# Attenuator_Channel.net
KiCad netlist of a schematic drawn in Altium Designer
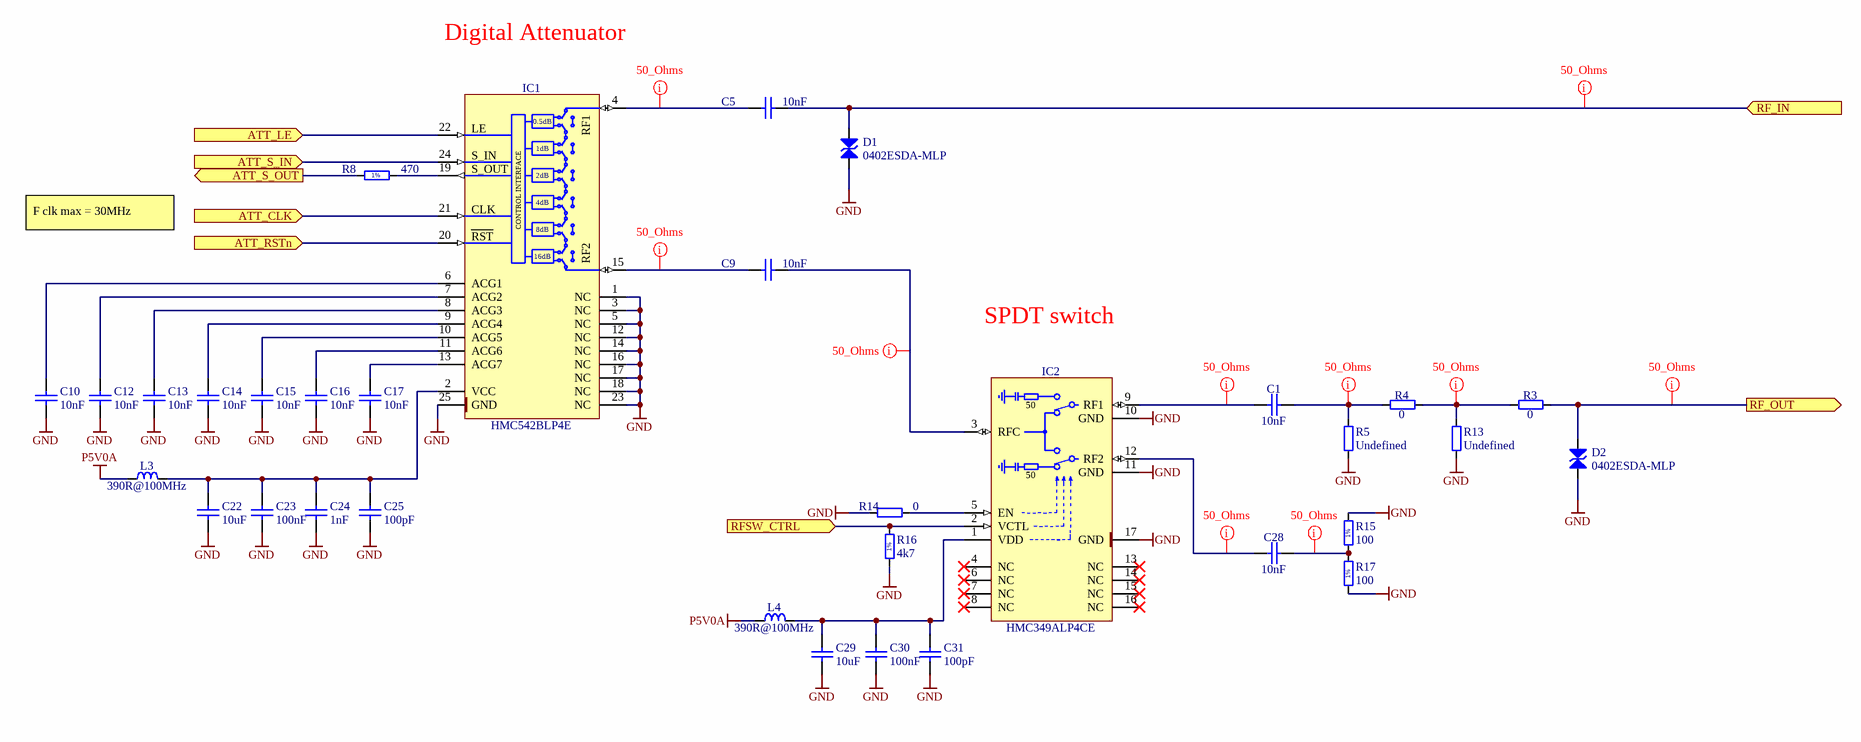
[diagram p0: Attenuator_Channel.SchDoc]

(export (version "E")
  (design (tool "Eeschema 10.0.6"))
  (components
    (comp (ref "C1")
      (value "10nF")
      (footprint "CAPC1005X55N")
      (description "Non-polarised capacitor")
      (fields
        (field (name "PART NUMBER") "CC0402_10NF_16V_10%_X7R")
        (field (name "VOLTAGE") "16V")
        (field (name "AUTHOR") "CERN DEM JLC")
      )
      (libsource (lib "Capacitors") (part "Capacitor - non polarized"))
    )
    (comp (ref "C5")
      (value "10nF")
      (footprint "CAPC1005X55N")
      (description "Non-polarised capacitor")
      (fields
        (field (name "PART NUMBER") "CC0402_10NF_16V_10%_X7R")
        (field (name "VOLTAGE") "16V")
        (field (name "AUTHOR") "CERN DEM JLC")
      )
      (libsource (lib "Capacitors") (part "Capacitor - non polarized"))
    )
    (comp (ref "C9")
      (value "10nF")
      (footprint "CAPC1005X55N")
      (description "Non-polarised capacitor")
      (fields
        (field (name "PART NUMBER") "CC0402_10NF_16V_10%_X7R")
        (field (name "VOLTAGE") "16V")
        (field (name "AUTHOR") "CERN DEM JLC")
      )
      (libsource (lib "Capacitors") (part "Capacitor - non polarized"))
    )
    (comp (ref "C10")
      (value "10nF")
      (footprint "CAPC1005X55N")
      (description "Non-polarised capacitor")
      (fields
        (field (name "PART NUMBER") "CC0402_10NF_16V_10%_X7R")
        (field (name "VOLTAGE") "16V")
        (field (name "AUTHOR") "CERN DEM JLC")
      )
      (libsource (lib "Capacitors") (part "Capacitor - non polarized"))
    )
    (comp (ref "C12")
      (value "10nF")
      (footprint "CAPC1005X55N")
      (description "Non-polarised capacitor")
      (fields
        (field (name "PART NUMBER") "CC0402_10NF_16V_10%_X7R")
        (field (name "VOLTAGE") "16V")
        (field (name "AUTHOR") "CERN DEM JLC")
      )
      (libsource (lib "Capacitors") (part "Capacitor - non polarized"))
    )
    (comp (ref "C13")
      (value "10nF")
      (footprint "CAPC1005X55N")
      (description "Non-polarised capacitor")
      (fields
        (field (name "PART NUMBER") "CC0402_10NF_16V_10%_X7R")
        (field (name "VOLTAGE") "16V")
        (field (name "AUTHOR") "CERN DEM JLC")
      )
      (libsource (lib "Capacitors") (part "Capacitor - non polarized"))
    )
    (comp (ref "C14")
      (value "10nF")
      (footprint "CAPC1005X55N")
      (description "Non-polarised capacitor")
      (fields
        (field (name "PART NUMBER") "CC0402_10NF_16V_10%_X7R")
        (field (name "VOLTAGE") "16V")
        (field (name "AUTHOR") "CERN DEM JLC")
      )
      (libsource (lib "Capacitors") (part "Capacitor - non polarized"))
    )
    (comp (ref "C15")
      (value "10nF")
      (footprint "CAPC1005X55N")
      (description "Non-polarised capacitor")
      (fields
        (field (name "PART NUMBER") "CC0402_10NF_16V_10%_X7R")
        (field (name "VOLTAGE") "16V")
        (field (name "AUTHOR") "CERN DEM JLC")
      )
      (libsource (lib "Capacitors") (part "Capacitor - non polarized"))
    )
    (comp (ref "C16")
      (value "10nF")
      (footprint "CAPC1005X55N")
      (description "Non-polarised capacitor")
      (fields
        (field (name "PART NUMBER") "CC0402_10NF_16V_10%_X7R")
        (field (name "VOLTAGE") "16V")
        (field (name "AUTHOR") "CERN DEM JLC")
      )
      (libsource (lib "Capacitors") (part "Capacitor - non polarized"))
    )
    (comp (ref "C17")
      (value "10nF")
      (footprint "CAPC1005X55N")
      (description "Non-polarised capacitor")
      (fields
        (field (name "PART NUMBER") "CC0402_10NF_16V_10%_X7R")
        (field (name "VOLTAGE") "16V")
        (field (name "AUTHOR") "CERN DEM JLC")
      )
      (libsource (lib "Capacitors") (part "Capacitor - non polarized"))
    )
    (comp (ref "C22")
      (value "10uF")
      (footprint "CAPC1608X80N")
      (description "Non-polarised capacitor")
      (fields
        (field (name "PART NUMBER") "CC0603_10UF_16V_20%_X5R")
        (field (name "VOLTAGE") "16V")
        (field (name "AUTHOR") "CERN DEM MR")
      )
      (libsource (lib "Capacitors") (part "Capacitor - non polarized"))
    )
    (comp (ref "C23")
      (value "100nF")
      (footprint "CAPC1005X55N")
      (description "Non-polarised capacitor")
      (fields
        (field (name "PART NUMBER") "CC0402_100NF_16V_10%_X5R")
        (field (name "VOLTAGE") "16V")
        (field (name "AUTHOR") "CERN DEM JLC")
      )
      (libsource (lib "Capacitors") (part "Capacitor - non polarized"))
    )
    (comp (ref "C24")
      (value "1nF")
      (footprint "CAPC1005X55N")
      (description "Non-polarised capacitor")
      (fields
        (field (name "PART NUMBER") "CC0402_1NF_50V_10%_X7R")
        (field (name "VOLTAGE") "50V")
        (field (name "AUTHOR") "CERN DEM JLC")
      )
      (libsource (lib "Capacitors") (part "Capacitor - non polarized"))
    )
    (comp (ref "C25")
      (value "100pF")
      (footprint "CAPC1005X55N")
      (description "Non-polarised capacitor")
      (fields
        (field (name "PART NUMBER") "CC0402_100PF_50V_5%_C0G")
        (field (name "VOLTAGE") "50V")
        (field (name "AUTHOR") "CERN DEM JLC")
      )
      (libsource (lib "Capacitors") (part "Capacitor - non polarized"))
    )
    (comp (ref "C28")
      (value "10nF")
      (footprint "CAPC1005X55N")
      (description "Non-polarised capacitor")
      (fields
        (field (name "PART NUMBER") "CC0402_10NF_16V_10%_X7R")
        (field (name "VOLTAGE") "16V")
        (field (name "AUTHOR") "CERN DEM JLC")
      )
      (libsource (lib "Capacitors") (part "Capacitor - non polarized"))
    )
    (comp (ref "C29")
      (value "10uF")
      (footprint "CAPC1608X80N")
      (description "Non-polarised capacitor")
      (fields
        (field (name "PART NUMBER") "CC0603_10UF_16V_20%_X5R")
        (field (name "VOLTAGE") "16V")
        (field (name "AUTHOR") "CERN DEM MR")
      )
      (libsource (lib "Capacitors") (part "Capacitor - non polarized"))
    )
    (comp (ref "C30")
      (value "100nF")
      (footprint "CAPC1005X55N")
      (description "Non-polarised capacitor")
      (fields
        (field (name "PART NUMBER") "CC0402_100NF_16V_10%_X5R")
        (field (name "VOLTAGE") "16V")
        (field (name "AUTHOR") "CERN DEM JLC")
      )
      (libsource (lib "Capacitors") (part "Capacitor - non polarized"))
    )
    (comp (ref "C31")
      (value "100pF")
      (footprint "CAPC1005X55N")
      (description "Non-polarised capacitor")
      (fields
        (field (name "PART NUMBER") "CC0402_100PF_50V_5%_C0G")
        (field (name "VOLTAGE") "50V")
        (field (name "AUTHOR") "CERN DEM JLC")
      )
      (libsource (lib "Capacitors") (part "Capacitor - non polarized"))
    )
    (comp (ref "D1")
      (value "0402ESDA-MLP")
      (footprint "EATON_0402ESDA-MLP")
      (description "Transient Voltage Suppressor Diode (Bi-Directional)")
      (fields
        (field (name "VOLTAGE") "8kV")
        (field (name "MANUFACTURER") "EATON")
        (field (name "AUTHOR") "CERN DEM MR")
      )
      (libsource (lib "ICs And Semiconductors") (part "Diode TVS Bi-Directional"))
    )
    (comp (ref "D2")
      (value "0402ESDA-MLP")
      (footprint "EATON_0402ESDA-MLP")
      (description "Transient Voltage Suppressor Diode (Bi-Directional)")
      (fields
        (field (name "VOLTAGE") "8kV")
        (field (name "MANUFACTURER") "EATON")
        (field (name "AUTHOR") "CERN DEM MR")
      )
      (libsource (lib "ICs And Semiconductors") (part "Diode TVS Bi-Directional"))
    )
    (comp (ref "IC1")
      (value "HMC542BLP4E")
      (footprint "QFN50P400X400X100-25N-S295")
      (description "0.5dB LSB GaAs MMIC 6-bit Digital Serial Control Attenuator, DC - 4GHz")
      (fields (field (name "MANUFACTURER") "HITTITE MICROWAVE CORP") (field (name "AUTHOR") "CERN DEM JMW"))
      (libsource (lib "ICs And Semiconductors") (part "HMC542BLP4E"))
    )
    (comp (ref "IC2")
      (value "HMC349ALP4CE")
      (footprint "QFN65P400X400X100-17N-S255")
      (description "DC-4GHz High Isolation SPDT Non-Reflective Switch")
      (fields (field (name "MANUFACTURER") "ANALOG DEVICES") (field (name "AUTHOR") "CERN DEM JLC"))
      (libsource (lib "ICs And Semiconductors") (part "HMC349ALP4CE"))
    )
    (comp (ref "L3")
      (value "390R@100MHz")
      (footprint "INDC1608X95N")
      (description "Inductor")
      (fields
        (field (name "PART NUMBER") "IND0603_TDK_MPZ1608R391A")
        (field (name "POWER") "1.2A")
        (field (name "AUTHOR") "CERN DEM JLC")
      )
      (libsource (lib "Inductors & Transformers") (part "Inductor"))
    )
    (comp (ref "L4")
      (value "390R@100MHz")
      (footprint "INDC1608X95N")
      (description "Inductor")
      (fields
        (field (name "PART NUMBER") "IND0603_TDK_MPZ1608R391A")
        (field (name "POWER") "1.2A")
        (field (name "AUTHOR") "CERN DEM JLC")
      )
      (libsource (lib "Inductors & Transformers") (part "Inductor"))
    )
    (comp (ref "R3")
      (value "0")
      (footprint "RESC1005X40N")
      (description "Resistor")
      (fields
        (field (name "PART NUMBER") "R0402_0R_JUMPER")
        (field (name "MANUFACTURER") "GENERIC")
        (field (name "AUTHOR") "CERN DEM JLC")
      )
      (libsource (lib "Resistors") (part "Resistor"))
    )
    (comp (ref "R4")
      (value "0")
      (footprint "RESC1005X40N")
      (description "Resistor")
      (fields
        (field (name "PART NUMBER") "R0402_0R_JUMPER")
        (field (name "MANUFACTURER") "GENERIC")
        (field (name "AUTHOR") "CERN DEM JLC")
      )
      (libsource (lib "Resistors") (part "Resistor"))
    )
    (comp (ref "R5")
      (value "Undefined")
      (footprint "RESC1005X40N")
      (description "Resistor")
      (fields (field (name "PART NUMBER") "R0402_NO-VALUE") (field (name "AUTHOR") "CERN DEM JLC"))
      (libsource (lib "Resistors") (part "Resistor"))
    )
    (comp (ref "R8")
      (value "470")
      (footprint "RESC1005X40N")
      (description "Resistor - 1%")
      (fields
        (field (name "PART NUMBER") "R0402_470R_1%_0.0625W_100PPM")
        (field (name "POWER") "0.0625W")
        (field (name "AUTHOR") "CERN DEM JLC")
      )
      (libsource (lib "Resistors") (part "Resistor - 1%"))
    )
    (comp (ref "R13")
      (value "Undefined")
      (footprint "RESC1005X40N")
      (description "Resistor")
      (fields (field (name "PART NUMBER") "R0402_NO-VALUE") (field (name "AUTHOR") "CERN DEM JLC"))
      (libsource (lib "Resistors") (part "Resistor"))
    )
    (comp (ref "R14")
      (value "0")
      (footprint "RESC1005X40N")
      (description "Resistor")
      (fields
        (field (name "PART NUMBER") "R0402_0R_JUMPER")
        (field (name "MANUFACTURER") "GENERIC")
        (field (name "AUTHOR") "CERN DEM JLC")
      )
      (libsource (lib "Resistors") (part "Resistor"))
    )
    (comp (ref "R15")
      (value "100")
      (footprint "RESC1005X40N")
      (description "Resistor - 1%")
      (fields
        (field (name "PART NUMBER") "R0402_100R_1%_0.0625W_100PPM")
        (field (name "POWER") "0.0625W")
        (field (name "AUTHOR") "CERN DEM JLC")
      )
      (libsource (lib "Resistors") (part "Resistor - 1%"))
    )
    (comp (ref "R16")
      (value "4k7")
      (footprint "RESC1005X40N")
      (description "Resistor - 1%")
      (fields
        (field (name "PART NUMBER") "R0402_4K7_1%_0.0625W_100PPM")
        (field (name "POWER") "0.0625W")
        (field (name "AUTHOR") "CERN DEM JLC")
      )
      (libsource (lib "Resistors") (part "Resistor - 1%"))
    )
    (comp (ref "R17")
      (value "100")
      (footprint "RESC1005X40N")
      (description "Resistor - 1%")
      (fields
        (field (name "PART NUMBER") "R0402_100R_1%_0.0625W_100PPM")
        (field (name "POWER") "0.0625W")
        (field (name "AUTHOR") "CERN DEM JLC")
      )
      (libsource (lib "Resistors") (part "Resistor - 1%"))
    )
  )
  (nets
    (net (code "1") (name "/ATT_CLK") (class "Default")
      (node (ref "IC1") (pin "21") (pinfunction "SHIFT_CLOCK_21") (pintype "input"))
    )
    (net (code "2") (name "/ATT_LE") (class "Default")
      (node (ref "IC1") (pin "22") (pinfunction "LATCH_ENABLE_22") (pintype "input"))
    )
    (net (code "3") (name "/ATT_RSTn") (class "Default")
      (node (ref "IC1") (pin "20") (pinfunction "~{RESET}_20") (pintype "input"))
    )
    (net (code "4") (name "/ATT_S_IN") (class "Default")
      (node (ref "IC1") (pin "24") (pinfunction "SERIAL_INPUT_24") (pintype "input"))
    )
    (net (code "5") (name "/ATT_S_OUT") (class "Default")
      (node (ref "R8") (pin "1") (pinfunction "1_1") (pintype "passive"))
    )
    (net (code "6") (name "/RFSW_CTRL") (class "Default")
      (node (ref "IC2") (pin "2") (pinfunction "VCTL_2") (pintype "input"))
      (node (ref "R16") (pin "2") (pinfunction "2_2") (pintype "passive"))
    )
    (net (code "7") (name "/RF_IN") (class "Default")
      (node (ref "C5") (pin "2") (pinfunction "2_2") (pintype "passive"))
      (node (ref "D1") (pin "2") (pinfunction "2_2") (pintype "passive"))
    )
    (net (code "8") (name "/RF_OUT") (class "Default")
      (node (ref "D2") (pin "2") (pinfunction "2_2") (pintype "passive"))
      (node (ref "R3") (pin "2") (pinfunction "2_2") (pintype "passive"))
    )
    (net (code "9") (name "GND") (class "Default")
      (node (ref "C10") (pin "1") (pinfunction "1_1") (pintype "passive"))
      (node (ref "C12") (pin "1") (pinfunction "1_1") (pintype "passive"))
      (node (ref "C13") (pin "1") (pinfunction "1_1") (pintype "passive"))
      (node (ref "C14") (pin "1") (pinfunction "1_1") (pintype "passive"))
      (node (ref "C15") (pin "1") (pinfunction "1_1") (pintype "passive"))
      (node (ref "C16") (pin "1") (pinfunction "1_1") (pintype "passive"))
      (node (ref "C17") (pin "1") (pinfunction "1_1") (pintype "passive"))
      (node (ref "C22") (pin "1") (pinfunction "1_1") (pintype "passive"))
      (node (ref "C23") (pin "1") (pinfunction "1_1") (pintype "passive"))
      (node (ref "C24") (pin "1") (pinfunction "1_1") (pintype "passive"))
      (node (ref "C25") (pin "1") (pinfunction "1_1") (pintype "passive"))
      (node (ref "C29") (pin "1") (pinfunction "1_1") (pintype "passive"))
      (node (ref "C30") (pin "1") (pinfunction "1_1") (pintype "passive"))
      (node (ref "C31") (pin "1") (pinfunction "1_1") (pintype "passive"))
      (node (ref "D1") (pin "1") (pinfunction "1_1") (pintype "passive"))
      (node (ref "D2") (pin "1") (pinfunction "1_1") (pintype "passive"))
      (node (ref "IC1") (pin "1") (pinfunction "NC_1") (pintype "passive"))
      (node (ref "IC1") (pin "12") (pinfunction "NC_12") (pintype "passive"))
      (node (ref "IC1") (pin "14") (pinfunction "NC_14") (pintype "passive"))
      (node (ref "IC1") (pin "16") (pinfunction "NC_16") (pintype "passive"))
      (node (ref "IC1") (pin "17") (pinfunction "NC_17") (pintype "passive"))
      (node (ref "IC1") (pin "18") (pinfunction "NC_18") (pintype "passive"))
      (node (ref "IC1") (pin "23") (pinfunction "NC_23") (pintype "passive"))
      (node (ref "IC1") (pin "25") (pinfunction "GND_25") (pintype "power_in"))
      (node (ref "IC1") (pin "3") (pinfunction "NC_3") (pintype "passive"))
      (node (ref "IC1") (pin "5") (pinfunction "NC_5") (pintype "passive"))
      (node (ref "IC2") (pin "10") (pinfunction "GND_10") (pintype "power_in"))
      (node (ref "IC2") (pin "11") (pinfunction "GND_11") (pintype "power_in"))
      (node (ref "IC2") (pin "17") (pinfunction "GND_17") (pintype "power_in"))
      (node (ref "R13") (pin "1") (pinfunction "1_1") (pintype "passive"))
      (node (ref "R14") (pin "1") (pinfunction "1_1") (pintype "passive"))
      (node (ref "R15") (pin "2") (pinfunction "2_2") (pintype "passive"))
      (node (ref "R16") (pin "1") (pinfunction "1_1") (pintype "passive"))
      (node (ref "R17") (pin "1") (pinfunction "1_1") (pintype "passive"))
      (node (ref "R5") (pin "1") (pinfunction "1_1") (pintype "passive"))
    )
    (net (code "10") (name "Net-(C1-Pad2)") (class "Default")
      (node (ref "C1") (pin "2") (pinfunction "2_2") (pintype "passive"))
      (node (ref "R4") (pin "1") (pinfunction "1_1") (pintype "passive"))
      (node (ref "R5") (pin "2") (pinfunction "2_2") (pintype "passive"))
    )
    (net (code "11") (name "Net-(C28-Pad2)") (class "Default")
      (node (ref "C28") (pin "2") (pinfunction "2_2") (pintype "passive"))
      (node (ref "R15") (pin "1") (pinfunction "1_1") (pintype "passive"))
      (node (ref "R17") (pin "2") (pinfunction "2_2") (pintype "passive"))
    )
    (net (code "12") (name "Net-(IC1-ACG1)") (class "Default")
      (node (ref "C10") (pin "2") (pinfunction "2_2") (pintype "passive"))
      (node (ref "IC1") (pin "6") (pinfunction "ACG1_6") (pintype "passive"))
    )
    (net (code "13") (name "Net-(IC1-ACG2)") (class "Default")
      (node (ref "C12") (pin "2") (pinfunction "2_2") (pintype "passive"))
      (node (ref "IC1") (pin "7") (pinfunction "ACG2_7") (pintype "passive"))
    )
    (net (code "14") (name "Net-(IC1-ACG3)") (class "Default")
      (node (ref "C13") (pin "2") (pinfunction "2_2") (pintype "passive"))
      (node (ref "IC1") (pin "8") (pinfunction "ACG3_8") (pintype "passive"))
    )
    (net (code "15") (name "Net-(IC1-ACG4)") (class "Default")
      (node (ref "C14") (pin "2") (pinfunction "2_2") (pintype "passive"))
      (node (ref "IC1") (pin "9") (pinfunction "ACG4_9") (pintype "passive"))
    )
    (net (code "16") (name "Net-(IC1-ACG5)") (class "Default")
      (node (ref "C15") (pin "2") (pinfunction "2_2") (pintype "passive"))
      (node (ref "IC1") (pin "10") (pinfunction "ACG5_10") (pintype "passive"))
    )
    (net (code "17") (name "Net-(IC1-ACG6)") (class "Default")
      (node (ref "C16") (pin "2") (pinfunction "2_2") (pintype "passive"))
      (node (ref "IC1") (pin "11") (pinfunction "ACG6_11") (pintype "passive"))
    )
    (net (code "18") (name "Net-(IC1-ACG7)") (class "Default")
      (node (ref "C17") (pin "2") (pinfunction "2_2") (pintype "passive"))
      (node (ref "IC1") (pin "13") (pinfunction "ACG7_13") (pintype "passive"))
    )
    (net (code "19") (name "Net-(IC1-RF1)") (class "Default")
      (node (ref "C5") (pin "1") (pinfunction "1_1") (pintype "passive"))
      (node (ref "IC1") (pin "4") (pinfunction "RF1_4") (pintype "bidirectional"))
    )
    (net (code "20") (name "Net-(IC1-RF2)") (class "Default")
      (node (ref "C9") (pin "1") (pinfunction "1_1") (pintype "passive"))
      (node (ref "IC1") (pin "15") (pinfunction "RF2_15") (pintype "bidirectional"))
    )
    (net (code "21") (name "Net-(IC1-SERIAL_OUTPUT)") (class "Default")
      (node (ref "IC1") (pin "19") (pinfunction "SERIAL_OUTPUT_19") (pintype "output"))
      (node (ref "R8") (pin "2") (pinfunction "2_2") (pintype "passive"))
    )
    (net (code "22") (name "Net-(IC1-VCC)") (class "Default")
      (node (ref "C22") (pin "2") (pinfunction "2_2") (pintype "passive"))
      (node (ref "C23") (pin "2") (pinfunction "2_2") (pintype "passive"))
      (node (ref "C24") (pin "2") (pinfunction "2_2") (pintype "passive"))
      (node (ref "C25") (pin "2") (pinfunction "2_2") (pintype "passive"))
      (node (ref "IC1") (pin "2") (pinfunction "VCC_2") (pintype "power_in"))
      (node (ref "L3") (pin "2") (pinfunction "2_2") (pintype "passive"))
    )
    (net (code "23") (name "Net-(IC2-EN)") (class "Default")
      (node (ref "IC2") (pin "5") (pinfunction "EN_5") (pintype "input"))
      (node (ref "R14") (pin "2") (pinfunction "2_2") (pintype "passive"))
    )
    (net (code "24") (name "Net-(IC2-RF1)") (class "Default")
      (node (ref "C1") (pin "1") (pinfunction "1_1") (pintype "passive"))
      (node (ref "IC2") (pin "9") (pinfunction "RF1_9") (pintype "bidirectional"))
    )
    (net (code "25") (name "Net-(IC2-RF2)") (class "Default")
      (node (ref "C28") (pin "1") (pinfunction "1_1") (pintype "passive"))
      (node (ref "IC2") (pin "12") (pinfunction "RF2_12") (pintype "bidirectional"))
    )
    (net (code "26") (name "Net-(IC2-RFC)") (class "Default")
      (node (ref "C9") (pin "2") (pinfunction "2_2") (pintype "passive"))
      (node (ref "IC2") (pin "3") (pinfunction "RFC_3") (pintype "bidirectional"))
    )
    (net (code "27") (name "Net-(IC2-VDD)") (class "Default")
      (node (ref "C29") (pin "2") (pinfunction "2_2") (pintype "passive"))
      (node (ref "C30") (pin "2") (pinfunction "2_2") (pintype "passive"))
      (node (ref "C31") (pin "2") (pinfunction "2_2") (pintype "passive"))
      (node (ref "IC2") (pin "1") (pinfunction "VDD_1") (pintype "power_in"))
      (node (ref "L4") (pin "2") (pinfunction "2_2") (pintype "passive"))
    )
    (net (code "28") (name "Net-(R13-Pad2)") (class "Default")
      (node (ref "R13") (pin "2") (pinfunction "2_2") (pintype "passive"))
      (node (ref "R3") (pin "1") (pinfunction "1_1") (pintype "passive"))
      (node (ref "R4") (pin "2") (pinfunction "2_2") (pintype "passive"))
    )
    (net (code "29") (name "P5V0A") (class "Default")
      (node (ref "L3") (pin "1") (pinfunction "1_1") (pintype "passive"))
      (node (ref "L4") (pin "1") (pinfunction "1_1") (pintype "passive"))
    )
    (net (code "30") (name "unconnected-(IC2-NC-Pad4)") (class "Default")
      (node (ref "IC2") (pin "4") (pinfunction "NC_4") (pintype "passive+no_connect"))
    )
    (net (code "31") (name "unconnected-(IC2-NC-Pad6)") (class "Default")
      (node (ref "IC2") (pin "6") (pinfunction "NC_6") (pintype "passive+no_connect"))
    )
    (net (code "32") (name "unconnected-(IC2-NC-Pad7)") (class "Default")
      (node (ref "IC2") (pin "7") (pinfunction "NC_7") (pintype "passive+no_connect"))
    )
    (net (code "33") (name "unconnected-(IC2-NC-Pad8)") (class "Default")
      (node (ref "IC2") (pin "8") (pinfunction "NC_8") (pintype "passive+no_connect"))
    )
    (net (code "34") (name "unconnected-(IC2-NC-Pad13)") (class "Default")
      (node (ref "IC2") (pin "13") (pinfunction "NC_13") (pintype "passive+no_connect"))
    )
    (net (code "35") (name "unconnected-(IC2-NC-Pad14)") (class "Default")
      (node (ref "IC2") (pin "14") (pinfunction "NC_14") (pintype "passive+no_connect"))
    )
    (net (code "36") (name "unconnected-(IC2-NC-Pad15)") (class "Default")
      (node (ref "IC2") (pin "15") (pinfunction "NC_15") (pintype "passive+no_connect"))
    )
    (net (code "37") (name "unconnected-(IC2-NC-Pad16)") (class "Default")
      (node (ref "IC2") (pin "16") (pinfunction "NC_16") (pintype "passive+no_connect"))
    )
  )
)
